# controls.net
KiCad netlist of a schematic drawn in EAGLE
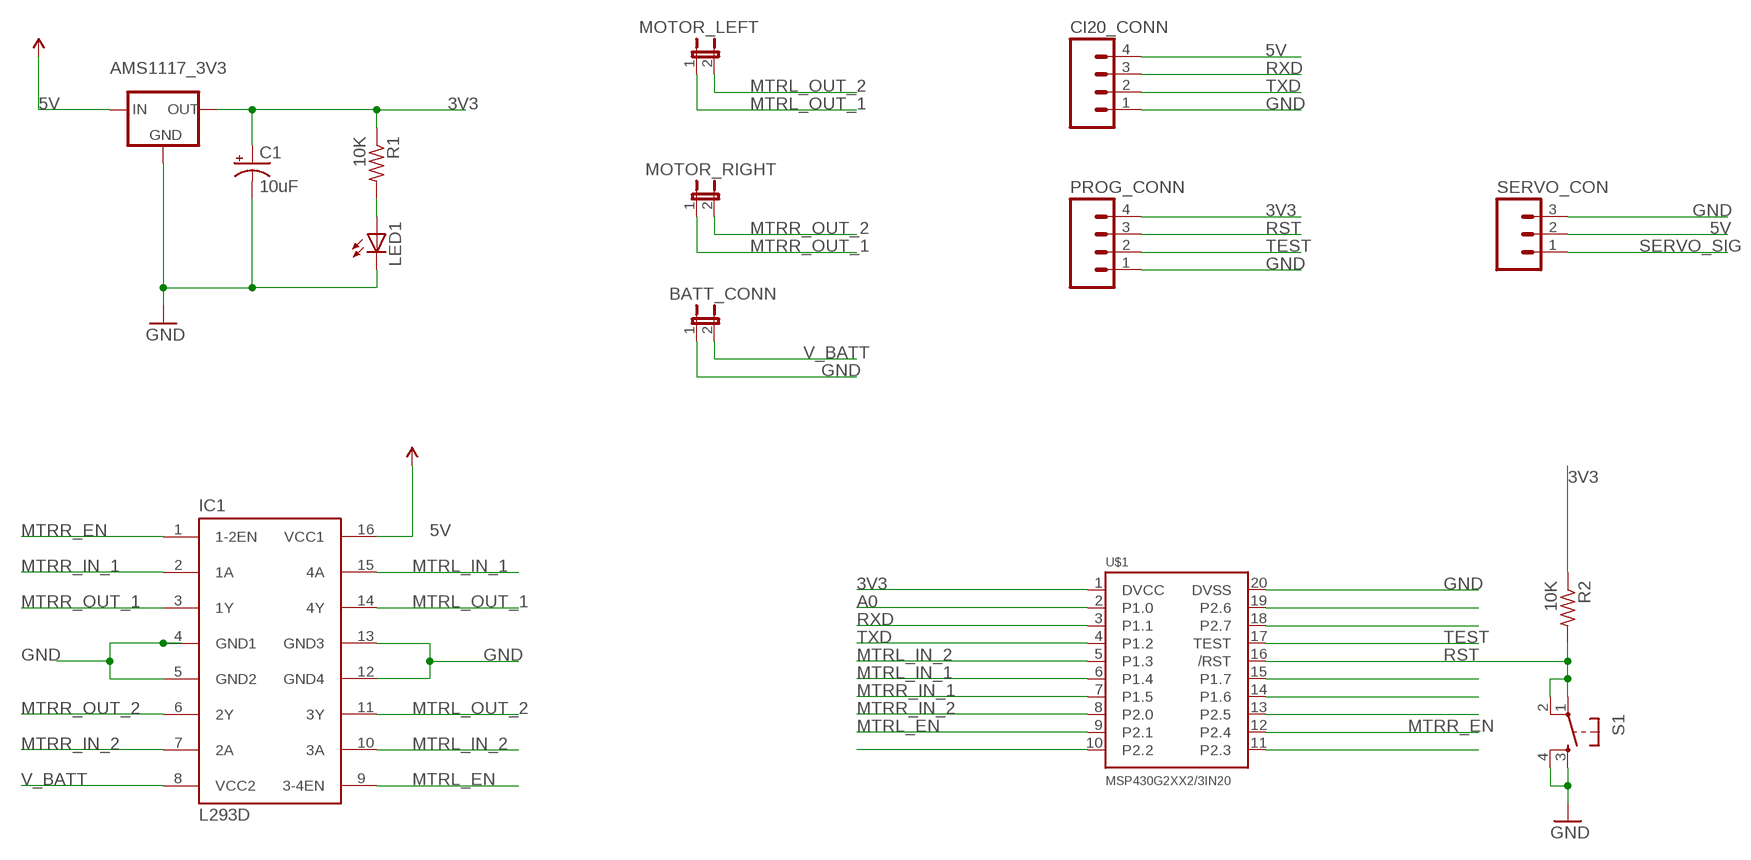
[diagram p0: schematic, sheet 1]

(export (version "E")
  (design (tool "Eeschema 10.0.6"))
  (components
    (comp (ref "AMS1117_3V3")
      (value "V_REG_LD1117VXX")
      (footprint "eagle-import:78XXL")
      (libsource (lib "eagle-import") (part "V_REG_LD1117VXX"))
    )
    (comp (ref "BATT_CONN")
      (value "JUMPER-2PTH")
      (footprint "eagle-import:1X02")
      (libsource (lib "eagle-import") (part "JUMPER-2PTH"))
    )
    (comp (ref "C1")
      (value "10uF")
      (footprint "eagle-import:E2,5-6")
      (libsource (lib "eagle-import") (part "CPOL-USE2.5-6"))
    )
    (comp (ref "CI20_CONN")
      (value "M04PTH")
      (footprint "eagle-import:1X04")
      (libsource (lib "eagle-import") (part "M04PTH"))
    )
    (comp (ref "IC1")
      (value "L293D")
      (footprint "eagle-import:DIL16")
      (libsource (lib "eagle-import") (part "L293D"))
    )
    (comp (ref "LED1")
      (value "LED5MM")
      (footprint "eagle-import:LED5MM")
      (libsource (lib "eagle-import") (part "LED5MM"))
    )
    (comp (ref "MOTOR_LEFT")
      (value "JUMPER-2PTH")
      (footprint "eagle-import:1X02")
      (libsource (lib "eagle-import") (part "JUMPER-2PTH"))
    )
    (comp (ref "MOTOR_RIGHT")
      (value "JUMPER-2PTH")
      (footprint "eagle-import:1X02")
      (libsource (lib "eagle-import") (part "JUMPER-2PTH"))
    )
    (comp (ref "PROG_CONN")
      (value "M04PTH")
      (footprint "eagle-import:1X04")
      (libsource (lib "eagle-import") (part "M04PTH"))
    )
    (comp (ref "R1")
      (value "10K")
      (footprint "eagle-import:0207_12")
      (libsource (lib "eagle-import") (part "R-US_0207/12"))
    )
    (comp (ref "R2")
      (value "10K")
      (footprint "eagle-import:0207_12")
      (libsource (lib "eagle-import") (part "R-US_0207/12"))
    )
    (comp (ref "S1")
      (value "TAC_SWITCHPTH")
      (footprint "eagle-import:TACTILE-PTH")
      (libsource (lib "eagle-import") (part "TAC_SWITCHPTH"))
    )
    (comp (ref "SERVO_CON")
      (value "M03PTH")
      (footprint "eagle-import:1X03")
      (libsource (lib "eagle-import") (part "M03PTH"))
    )
    (comp (ref "U$1")
      (value "MSP430G2XX2/3IN20")
      (footprint "eagle-import:DIL20")
      (libsource (lib "eagle-import") (part "MSP430G2XX2/3IN20"))
    )
  )
  (nets
    (net (code "1") (name "/3V3") (class "Default")
      (node (ref "AMS1117_3V3") (pin "GND") (pinfunction "OUT_GND") (pintype "output"))
      (node (ref "C1") (pin "+") (pinfunction "+_+") (pintype "passive"))
      (node (ref "PROG_CONN") (pin "4") (pinfunction "4_4") (pintype "passive"))
      (node (ref "R1") (pin "1") (pinfunction "1_1") (pintype "passive"))
      (node (ref "R2") (pin "1") (pinfunction "1_1") (pintype "passive"))
      (node (ref "U$1") (pin "1") (pinfunction "DVCC_1") (pintype "power_in"))
    )
    (net (code "2") (name "/A0") (class "Default")
      (node (ref "U$1") (pin "2") (pinfunction "P1.0_2") (pintype "bidirectional"))
    )
    (net (code "3") (name "/MTRL_EN") (class "Default")
      (node (ref "IC1") (pin "9") (pinfunction "3-4EN_9") (pintype "input"))
      (node (ref "U$1") (pin "9") (pinfunction "P2.1_9") (pintype "bidirectional"))
    )
    (net (code "4") (name "/MTRL_IN_1") (class "Default")
      (node (ref "IC1") (pin "15") (pinfunction "4A_15") (pintype "input"))
      (node (ref "U$1") (pin "6") (pinfunction "P1.4_6") (pintype "bidirectional"))
    )
    (net (code "5") (name "/MTRL_IN_2") (class "Default")
      (node (ref "IC1") (pin "10") (pinfunction "3A_10") (pintype "input"))
      (node (ref "U$1") (pin "5") (pinfunction "P1.3_5") (pintype "bidirectional"))
    )
    (net (code "6") (name "/MTRL_OUT_1") (class "Default")
      (node (ref "IC1") (pin "14") (pinfunction "4Y_14") (pintype "output"))
      (node (ref "MOTOR_LEFT") (pin "1") (pinfunction "1_1") (pintype "passive"))
    )
    (net (code "7") (name "/MTRL_OUT_2") (class "Default")
      (node (ref "IC1") (pin "11") (pinfunction "3Y_11") (pintype "output"))
      (node (ref "MOTOR_LEFT") (pin "2") (pinfunction "2_2") (pintype "passive"))
    )
    (net (code "8") (name "/MTRR_EN") (class "Default")
      (node (ref "IC1") (pin "1") (pinfunction "1-2EN_1") (pintype "input"))
      (node (ref "U$1") (pin "12") (pinfunction "P2.4_12") (pintype "bidirectional"))
    )
    (net (code "9") (name "/MTRR_IN_1") (class "Default")
      (node (ref "IC1") (pin "2") (pinfunction "1A_2") (pintype "input"))
      (node (ref "U$1") (pin "7") (pinfunction "P1.5_7") (pintype "bidirectional"))
    )
    (net (code "10") (name "/MTRR_IN_2") (class "Default")
      (node (ref "IC1") (pin "7") (pinfunction "2A_7") (pintype "input"))
      (node (ref "U$1") (pin "8") (pinfunction "P2.0_8") (pintype "bidirectional"))
    )
    (net (code "11") (name "/MTRR_OUT_1") (class "Default")
      (node (ref "IC1") (pin "3") (pinfunction "1Y_3") (pintype "output"))
      (node (ref "MOTOR_RIGHT") (pin "1") (pinfunction "1_1") (pintype "passive"))
    )
    (net (code "12") (name "/MTRR_OUT_2") (class "Default")
      (node (ref "IC1") (pin "6") (pinfunction "2Y_6") (pintype "output"))
      (node (ref "MOTOR_RIGHT") (pin "2") (pinfunction "2_2") (pintype "passive"))
    )
    (net (code "13") (name "/RST") (class "Default")
      (node (ref "PROG_CONN") (pin "3") (pinfunction "3_3") (pintype "passive"))
      (node (ref "R2") (pin "2") (pinfunction "2_2") (pintype "passive"))
      (node (ref "S1") (pin "1") (pinfunction "1_1") (pintype "passive"))
      (node (ref "S1") (pin "2") (pinfunction "2_2") (pintype "passive"))
      (node (ref "U$1") (pin "16") (pinfunction "/RST_16") (pintype "bidirectional"))
    )
    (net (code "14") (name "/RXD") (class "Default")
      (node (ref "CI20_CONN") (pin "3") (pinfunction "3_3") (pintype "passive"))
      (node (ref "U$1") (pin "3") (pinfunction "P1.1_3") (pintype "bidirectional"))
    )
    (net (code "15") (name "/SERVO_SIG") (class "Default")
      (node (ref "SERVO_CON") (pin "1") (pinfunction "1_1") (pintype "passive"))
    )
    (net (code "16") (name "/TEST") (class "Default")
      (node (ref "PROG_CONN") (pin "2") (pinfunction "2_2") (pintype "passive"))
      (node (ref "U$1") (pin "17") (pinfunction "TEST_17") (pintype "bidirectional"))
    )
    (net (code "17") (name "/TXD") (class "Default")
      (node (ref "CI20_CONN") (pin "2") (pinfunction "2_2") (pintype "passive"))
      (node (ref "U$1") (pin "4") (pinfunction "P1.2_4") (pintype "bidirectional"))
    )
    (net (code "18") (name "/V_BATT") (class "Default")
      (node (ref "BATT_CONN") (pin "2") (pinfunction "2_2") (pintype "passive"))
      (node (ref "IC1") (pin "8") (pinfunction "VCC2_8") (pintype "power_in"))
    )
    (net (code "19") (name "GND") (class "Default")
      (node (ref "AMS1117_3V3") (pin "IN") (pinfunction "GND_IN") (pintype "input"))
      (node (ref "BATT_CONN") (pin "1") (pinfunction "1_1") (pintype "passive"))
      (node (ref "C1") (pin "-") (pinfunction "-_-") (pintype "passive"))
      (node (ref "CI20_CONN") (pin "1") (pinfunction "1_1") (pintype "passive"))
      (node (ref "IC1") (pin "12") (pinfunction "GND4_12") (pintype "power_in"))
      (node (ref "IC1") (pin "13") (pinfunction "GND3_13") (pintype "power_in"))
      (node (ref "IC1") (pin "4") (pinfunction "GND1_4") (pintype "power_in"))
      (node (ref "IC1") (pin "5") (pinfunction "GND2_5") (pintype "power_in"))
      (node (ref "LED1") (pin "K") (pinfunction "C_K") (pintype "passive"))
      (node (ref "PROG_CONN") (pin "1") (pinfunction "1_1") (pintype "passive"))
      (node (ref "S1") (pin "3") (pinfunction "3_3") (pintype "passive"))
      (node (ref "S1") (pin "4") (pinfunction "4_4") (pintype "passive"))
      (node (ref "SERVO_CON") (pin "3") (pinfunction "3_3") (pintype "passive"))
      (node (ref "U$1") (pin "20") (pinfunction "DVSS_20") (pintype "power_in"))
    )
    (net (code "20") (name "Net-(LED1-PadA)") (class "Default")
      (node (ref "LED1") (pin "A") (pinfunction "A_A") (pintype "passive"))
      (node (ref "R1") (pin "2") (pinfunction "2_2") (pintype "passive"))
    )
    (net (code "21") (name "VCC") (class "Default")
      (node (ref "AMS1117_3V3") (pin "OUT") (pinfunction "IN_OUT") (pintype "input"))
      (node (ref "CI20_CONN") (pin "4") (pinfunction "4_4") (pintype "passive"))
      (node (ref "IC1") (pin "16") (pinfunction "VCC1_16") (pintype "power_in"))
      (node (ref "SERVO_CON") (pin "2") (pinfunction "2_2") (pintype "passive"))
    )
    (net (code "22") (name "unconnected-(U$1-P1.6-Pad14)") (class "Default")
      (node (ref "U$1") (pin "14") (pinfunction "P1.6_14") (pintype "bidirectional"))
    )
    (net (code "23") (name "unconnected-(U$1-P1.7-Pad15)") (class "Default")
      (node (ref "U$1") (pin "15") (pinfunction "P1.7_15") (pintype "bidirectional"))
    )
    (net (code "24") (name "unconnected-(U$1-P2.2-Pad10)") (class "Default")
      (node (ref "U$1") (pin "10") (pinfunction "P2.2_10") (pintype "bidirectional"))
    )
    (net (code "25") (name "unconnected-(U$1-P2.3-Pad11)") (class "Default")
      (node (ref "U$1") (pin "11") (pinfunction "P2.3_11") (pintype "bidirectional"))
    )
    (net (code "26") (name "unconnected-(U$1-P2.5-Pad13)") (class "Default")
      (node (ref "U$1") (pin "13") (pinfunction "P2.5_13") (pintype "bidirectional"))
    )
    (net (code "27") (name "unconnected-(U$1-P2.6-Pad19)") (class "Default")
      (node (ref "U$1") (pin "19") (pinfunction "P2.6_19") (pintype "bidirectional"))
    )
    (net (code "28") (name "unconnected-(U$1-P2.7-Pad18)") (class "Default")
      (node (ref "U$1") (pin "18") (pinfunction "P2.7_18") (pintype "bidirectional"))
    )
  )
)
